# sub-1Ghz_radio.net
KiCad netlist of a schematic drawn in Altium Designer
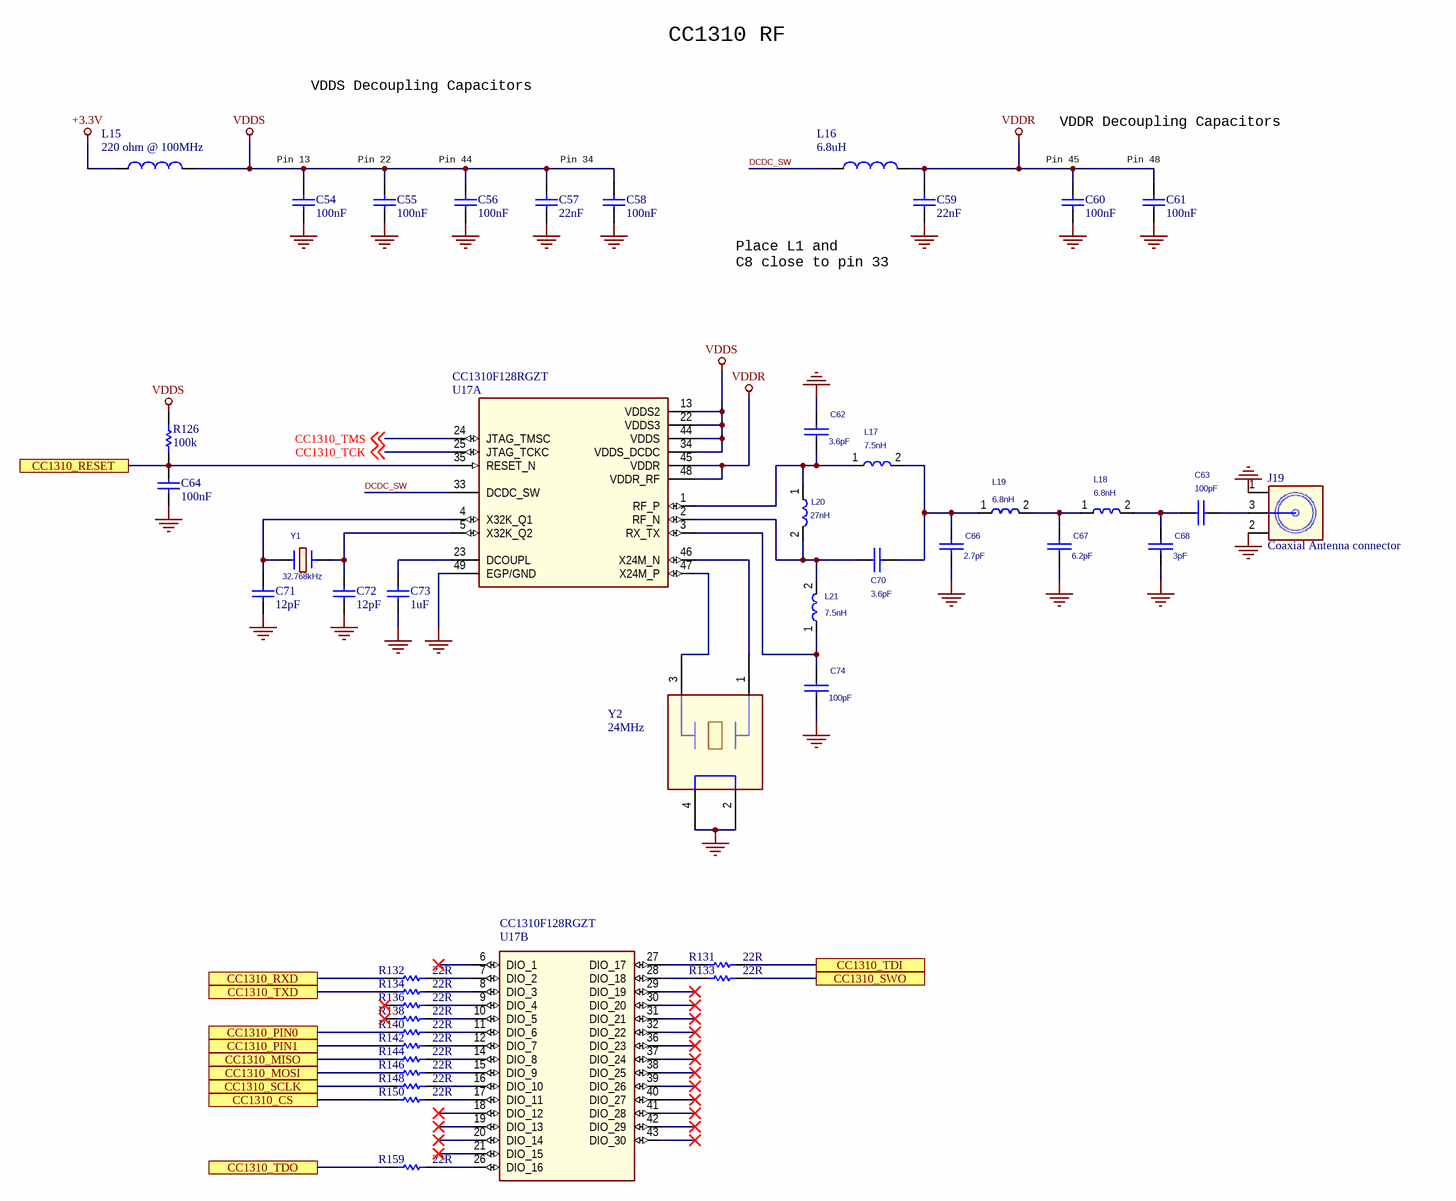
[diagram p0: sub-1Ghz_radio.SchDoc]

(export (version "E")
  (design (tool "Eeschema 10.0.6"))
  (components
    (comp (ref "C54")
      (value "100nF")
      (footprint "0603_[1608]")
      (description "Ceramic X7R 50V")
      (fields (field (name "PUBLISHER") "Altium Limited"))
      (libsource (lib "DEVELER_Library") (part "Cap"))
    )
    (comp (ref "C55")
      (value "100nF")
      (footprint "0603_[1608]")
      (description "Ceramic X7R 50V")
      (fields (field (name "PUBLISHER") "Altium Limited"))
      (libsource (lib "DEVELER_Library") (part "Cap"))
    )
    (comp (ref "C56")
      (value "100nF")
      (footprint "0603_[1608]")
      (description "Ceramic X7R 50V")
      (fields (field (name "PUBLISHER") "Altium Limited"))
      (libsource (lib "DEVELER_Library") (part "Cap"))
    )
    (comp (ref "C57")
      (value "22nF")
      (footprint "0603_[1608]")
      (description "Ceramic X7R 50V")
      (fields (field (name "PUBLISHER") "Altium Limited"))
      (libsource (lib "DEVELER_Library") (part "Cap"))
    )
    (comp (ref "C58")
      (value "100nF")
      (footprint "0603_[1608]")
      (description "Ceramic X7R 50V")
      (fields (field (name "PUBLISHER") "Altium Limited"))
      (libsource (lib "DEVELER_Library") (part "Cap"))
    )
    (comp (ref "C59")
      (value "22nF")
      (footprint "0603_[1608]")
      (description "Ceramic X7R 50V")
      (fields (field (name "PUBLISHER") "Altium Limited"))
      (libsource (lib "DEVELER_Library") (part "Cap"))
    )
    (comp (ref "C60")
      (value "100nF")
      (footprint "0603_[1608]")
      (description "Ceramic X7R 50V")
      (fields (field (name "PUBLISHER") "Altium Limited"))
      (libsource (lib "DEVELER_Library") (part "Cap"))
    )
    (comp (ref "C61")
      (value "100nF")
      (footprint "0603_[1608]")
      (description "Ceramic X7R 50V")
      (fields (field (name "PUBLISHER") "Altium Limited"))
      (libsource (lib "DEVELER_Library") (part "Cap"))
    )
    (comp (ref "C62")
      (value "3.6pF")
      (footprint "0402_[1005]")
      (description "CAPACITOR, CERAMIC C0G/NP0, 3.6pF, 50V, -0.25pF/+0.25pF, -55DEGC/+125DEGC, 0402, SMD")
      (fields (field (name "VOLTAGE") "CMAX") (field (name "VENDOR PART NUMBER") "GRM1555C1H3R6CA01D"))
      (libsource (lib "*") (part "CAPACITOR"))
    )
    (comp (ref "C63")
      (value "100pF")
      (footprint "0402_[1005]")
      (description "Ceramic COG 50V")
      (fields (field (name "VOLTAGE") "CMAX") (field (name "VENDOR PART NUMBER") "GRM1555C1H101JA01D"))
      (libsource (lib "*") (part "CAPACITOR"))
    )
    (comp (ref "C64")
      (value "100nF")
      (footprint "0603_[1608]")
      (description "Ceramic X7R 50V")
      (fields (field (name "PUBLISHER") "Altium Limited"))
      (libsource (lib "DEVELER_Library") (part "Cap"))
    )
    (comp (ref "C66")
      (value "2.7pF")
      (footprint "0402_[1005]")
      (description "CAPACITOR, CERAMIC C0G/NP0, 2.7pF, 50V, -0.25pF/+0.25pF, -55DEGC/+125DEGC, 0402, SMD")
      (fields (field (name "VOLTAGE") "CMAX") (field (name "MPN") "GRM1555C1H2R7CA01D"))
      (libsource (lib "*") (part "CAPACITOR"))
    )
    (comp (ref "C67")
      (value "6.2pF")
      (footprint "0402_[1005]")
      (description "CAPACITOR, CERAMIC C0G/NP0, 6.2pF, 50V, -0.25pF/+0.25pF, -55DEGC/+125DEGC, 0402, SMD")
      (fields (field (name "VOLTAGE") "CMAX") (field (name "MPN") "GRM1555C1H6R2CA01D"))
      (libsource (lib "*") (part "CAPACITOR"))
    )
    (comp (ref "C68")
      (value "3pF")
      (footprint "0402_[1005]")
      (description "CAPACITOR, CERAMIC C0G/NP0, 3pF, 50V, -0.25pF/+0.25pF, -55DEGC/+125DEGC, 0402, SMD")
      (fields (field (name "VOLTAGE") "CMAX") (field (name "MPN") "GRM1555C1H3R0CA01D"))
      (libsource (lib "*") (part "CAPACITOR"))
    )
    (comp (ref "C70")
      (value "3.6pF")
      (footprint "0402_[1005]")
      (description "CAPACITOR, CERAMIC C0G/NP0, 3.6pF, 50V, -0.25pF/+0.25pF, -55DEGC/+125DEGC, 0402, SMD")
      (fields (field (name "VOLTAGE") "CMAX") (field (name "VENDOR PART NUMBER") "GRM1555C1H3R6CA01D"))
      (libsource (lib "*") (part "CAPACITOR"))
    )
    (comp (ref "C71")
      (value "12pF")
      (footprint "0603_[1608]")
      (description "Ceramic X7R 50V")
      (fields (field (name "PUBLISHER") "Altium Limited"))
      (libsource (lib "DEVELER_Library") (part "Cap"))
    )
    (comp (ref "C72")
      (value "12pF")
      (footprint "0603_[1608]")
      (description "Ceramic X7R 50V")
      (fields (field (name "PUBLISHER") "Altium Limited"))
      (libsource (lib "DEVELER_Library") (part "Cap"))
    )
    (comp (ref "C73")
      (value "1uF")
      (footprint "0805_[2012]")
      (description "Ceramic X7R 50V")
      (fields (field (name "PUBLISHER") "Altium Limited"))
      (libsource (lib "DEVELER_Library") (part "Cap"))
    )
    (comp (ref "C74")
      (value "100pF")
      (footprint "0402_[1005]")
      (description "Ceramic COG 50V")
      (fields (field (name "VOLTAGE") "CMAX") (field (name "VENDOR PART NUMBER") "GRM1555C1H101JA01D"))
      (libsource (lib "*") (part "CAPACITOR"))
    )
    (comp (ref "J19")
      (value "Coaxial Antenna connector")
      (footprint "U.FL_COAXIAL_2.6x2.6MM_STRAIGHT_SMD")
      (description "U.FL serias")
      (libsource (lib "develer_library") (part "ANTENNA_3P_COAXIAL_CONNECTOR"))
    )
    (comp (ref "L15")
      (value "220 ohm @ 100MHz")
      (footprint "0805_[2012]")
      (description "WE 742792022")
      (libsource (lib "DEVELER_Library") (part "Ferrite Bead"))
    )
    (comp (ref "L16")
      (value "6.8uH")
      (footprint "0805_[2012]")
      (description "Inductor WE 742792022")
      (libsource (lib "DEVELER_Library") (part "Inductor"))
    )
    (comp (ref "L17")
      (value "7.5nH")
      (footprint "0402_[1005]")
      (description "INDUCTOR, RF, CHIP, NON-MAGNETIC CORE, 7.5nH, -5%/+5%, 0.3A, -55DEGC/+125DEGC, 0402, SMD")
      (fields (field (name "PART NUMBER") "03-07533") (field (name "VENDOR PART NUMBER") "LQG15HS7N5J02D"))
      (libsource (lib "*") (part "INDUCTOR"))
    )
    (comp (ref "L18")
      (value "6.8nH")
      (footprint "0402_[1005]")
      (description "INDUCTOR, RF, CHIP, NON-MAGNETIC CORE, 6.8nH, -5%/+5%, 0.3A, -55DEGC/+125DEGC, 0402, SMD")
      (fields (field (name "VENDOR PART NUMBER") "LQG15HS6N8J02D") (field (name "PART NUMBER") "03-07532"))
      (libsource (lib "*") (part "INDUCTOR"))
    )
    (comp (ref "L19")
      (value "6.8nH")
      (footprint "0402_[1005]")
      (description "INDUCTOR, RF, CHIP, NON-MAGNETIC CORE, 6.8nH, -5%/+5%, 0.3A, -55DEGC/+125DEGC, 0402, SMD")
      (fields (field (name "VENDOR PART NUMBER") "LQG15HS6N8J02D") (field (name "PART NUMBER") "03-07532"))
      (libsource (lib "*") (part "INDUCTOR"))
    )
    (comp (ref "L20")
      (value "27nH")
      (footprint "0402_[1005]")
      (description "INDUCTOR, RF, CHIP, NON-MAGNETIC CORE, 27nH, -5%/+5%, 0.3A, -55DEGC/+125DEGC, 0402, SMD")
      (fields (field (name "VENDOR PART NUMBER") "LQG15HS27NJ02D") (field (name "PART NUMBER") "03-07528"))
      (libsource (lib "*") (part "INDUCTOR"))
    )
    (comp (ref "L21")
      (value "7.5nH")
      (footprint "0402_[1005]")
      (description "INDUCTOR, RF, CHIP, NON-MAGNETIC CORE, 7.5nH, -5%/+5%, 0.3A, -55DEGC/+125DEGC, 0402, SMD")
      (fields (field (name "PART NUMBER") "03-07533") (field (name "VENDOR PART NUMBER") "LQG15HS7N5J02D"))
      (libsource (lib "*") (part "INDUCTOR"))
    )
    (comp (ref "R126")
      (value "100k")
      (footprint "0603_[1608]")
      (description "Resistor")
      (fields (field (name "PUBLISHER") "Altium Limited"))
      (libsource (lib "project42_lib") (part "Res1"))
    )
    (comp (ref "R131")
      (value "22R")
      (footprint "0603_[1608]")
      (description "Resistor")
      (fields (field (name "PUBLISHER") "Altium Limited"))
      (libsource (lib "DEVELER_Library") (part "Res1"))
    )
    (comp (ref "R132")
      (value "22R")
      (footprint "0603_[1608]")
      (description "Resistor")
      (fields (field (name "PUBLISHER") "Altium Limited"))
      (libsource (lib "DEVELER_Library") (part "Res1"))
    )
    (comp (ref "R133")
      (value "22R")
      (footprint "0603_[1608]")
      (description "Resistor")
      (fields (field (name "PUBLISHER") "Altium Limited"))
      (libsource (lib "DEVELER_Library") (part "Res1"))
    )
    (comp (ref "R134")
      (value "22R")
      (footprint "0603_[1608]")
      (description "Resistor")
      (fields (field (name "PUBLISHER") "Altium Limited"))
      (libsource (lib "DEVELER_Library") (part "Res1"))
    )
    (comp (ref "R136")
      (value "22R")
      (footprint "0603_[1608]")
      (description "Resistor")
      (fields (field (name "PUBLISHER") "Altium Limited"))
      (libsource (lib "DEVELER_Library") (part "Res1"))
    )
    (comp (ref "R138")
      (value "22R")
      (footprint "0603_[1608]")
      (description "Resistor")
      (fields (field (name "PUBLISHER") "Altium Limited"))
      (libsource (lib "DEVELER_Library") (part "Res1"))
    )
    (comp (ref "R140")
      (value "22R")
      (footprint "0603_[1608]")
      (description "Resistor")
      (fields (field (name "PUBLISHER") "Altium Limited"))
      (libsource (lib "DEVELER_Library") (part "Res1"))
    )
    (comp (ref "R142")
      (value "22R")
      (footprint "0603_[1608]")
      (description "Resistor")
      (fields (field (name "PUBLISHER") "Altium Limited"))
      (libsource (lib "DEVELER_Library") (part "Res1"))
    )
    (comp (ref "R144")
      (value "22R")
      (footprint "0603_[1608]")
      (description "Resistor")
      (fields (field (name "PUBLISHER") "Altium Limited"))
      (libsource (lib "DEVELER_Library") (part "Res1"))
    )
    (comp (ref "R146")
      (value "22R")
      (footprint "0603_[1608]")
      (description "Resistor")
      (fields (field (name "PUBLISHER") "Altium Limited"))
      (libsource (lib "DEVELER_Library") (part "Res1"))
    )
    (comp (ref "R148")
      (value "22R")
      (footprint "0603_[1608]")
      (description "Resistor")
      (fields (field (name "PUBLISHER") "Altium Limited"))
      (libsource (lib "DEVELER_Library") (part "Res1"))
    )
    (comp (ref "R150")
      (value "22R")
      (footprint "0603_[1608]")
      (description "Resistor")
      (fields (field (name "PUBLISHER") "Altium Limited"))
      (libsource (lib "DEVELER_Library") (part "Res1"))
    )
    (comp (ref "R159")
      (value "22R")
      (footprint "0603_[1608]")
      (description "Resistor")
      (fields (field (name "PUBLISHER") "Altium Limited"))
      (libsource (lib "DEVELER_Library") (part "Res1"))
    )
    (comp (ref "U17")
      (value "CC1310F128RGZT")
      (footprint "PQFN50P700X700X100-48N")
      (description "Texas CC1310 RF Cpu")
      (fields (field (name "DESIGNED_BY") "Artur Bielinski"))
      (libsource (lib "develer_library") (part "CC1310F128RGZT_VQFN48"))
    )
    (comp (ref "Y1")
      (value "32.768kHz")
      (footprint "CRYSTAL_3.2X1.5MM_2P_SMD")
      (description "CRYSTAL, RESONATOR, 32.768kHz, -20PPM/+20PPM, -40DEGC/+85DEGC, SMD")
      (fields (field (name "MPN") "FC-135 32.7680KA-AG0") (field (name "MANUFACTURER") "EPSON"))
      (libsource (lib "*") (part "CRYSTAL"))
    )
    (comp (ref "Y2")
      (value "24MHz")
      (footprint "CRYSTAL_3.2X2.5MM_4P_SMD")
      (description "Crystal")
      (libsource (lib "develer_library") (part "CRYSTAL-4p"))
    )
  )
  (nets
    (net (code "1") (name "+3.3V") (class "Default")
      (node (ref "L15") (pin "2") (pinfunction "2_2") (pintype "passive"))
    )
    (net (code "2") (name "/CC1310_CS") (class "Default")
      (node (ref "R150") (pin "2") (pinfunction "2_2") (pintype "passive"))
    )
    (net (code "3") (name "/CC1310_MISO") (class "Default")
      (node (ref "R144") (pin "2") (pinfunction "2_2") (pintype "passive"))
    )
    (net (code "4") (name "/CC1310_MOSI") (class "Default")
      (node (ref "R146") (pin "2") (pinfunction "2_2") (pintype "passive"))
    )
    (net (code "5") (name "/CC1310_PIN0") (class "Default")
      (node (ref "R140") (pin "2") (pinfunction "2_2") (pintype "passive"))
    )
    (net (code "6") (name "/CC1310_PIN1") (class "Default")
      (node (ref "R142") (pin "2") (pinfunction "2_2") (pintype "passive"))
    )
    (net (code "7") (name "/CC1310_RESET") (class "Default")
      (node (ref "C64") (pin "2") (pinfunction "2_2") (pintype "passive"))
      (node (ref "R126") (pin "2") (pinfunction "2_2") (pintype "passive"))
      (node (ref "U17") (pin "35") (pinfunction "RESET_N_35") (pintype "input"))
    )
    (net (code "8") (name "/CC1310_RXD") (class "Default")
      (node (ref "R132") (pin "2") (pinfunction "2_2") (pintype "passive"))
    )
    (net (code "9") (name "/CC1310_SCLK") (class "Default")
      (node (ref "R148") (pin "2") (pinfunction "2_2") (pintype "passive"))
    )
    (net (code "10") (name "/CC1310_SWO") (class "Default")
      (node (ref "R133") (pin "1") (pinfunction "1_1") (pintype "passive"))
    )
    (net (code "11") (name "/CC1310_TDI") (class "Default")
      (node (ref "R131") (pin "1") (pinfunction "1_1") (pintype "passive"))
    )
    (net (code "12") (name "/CC1310_TDO") (class "Default")
      (node (ref "R159") (pin "2") (pinfunction "2_2") (pintype "passive"))
    )
    (net (code "13") (name "/CC1310_TXD") (class "Default")
      (node (ref "R134") (pin "2") (pinfunction "2_2") (pintype "passive"))
    )
    (net (code "14") (name "/DCDC_SW") (class "Default")
      (node (ref "L16") (pin "2") (pinfunction "2_2") (pintype "passive"))
      (node (ref "U17") (pin "33") (pinfunction "DCDC_SW_33") (pintype "power_in"))
    )
    (net (code "15") (name "CC1310_TCK") (class "Default")
      (node (ref "U17") (pin "25") (pinfunction "JTAG_TCKC_25") (pintype "bidirectional"))
    )
    (net (code "16") (name "CC1310_TMS") (class "Default")
      (node (ref "U17") (pin "24") (pinfunction "JTAG_TMSC_24") (pintype "bidirectional"))
    )
    (net (code "17") (name "GND") (class "Default")
      (node (ref "C54") (pin "1") (pinfunction "1_1") (pintype "passive"))
      (node (ref "C55") (pin "1") (pinfunction "1_1") (pintype "passive"))
      (node (ref "C56") (pin "1") (pinfunction "1_1") (pintype "passive"))
      (node (ref "C57") (pin "1") (pinfunction "1_1") (pintype "passive"))
      (node (ref "C58") (pin "1") (pinfunction "1_1") (pintype "passive"))
      (node (ref "C59") (pin "1") (pinfunction "1_1") (pintype "passive"))
      (node (ref "C60") (pin "1") (pinfunction "1_1") (pintype "passive"))
      (node (ref "C61") (pin "1") (pinfunction "1_1") (pintype "passive"))
      (node (ref "C62") (pin "1") (pinfunction "1_1") (pintype "passive"))
      (node (ref "C64") (pin "1") (pinfunction "1_1") (pintype "passive"))
      (node (ref "C66") (pin "2") (pinfunction "2_2") (pintype "passive"))
      (node (ref "C67") (pin "2") (pinfunction "2_2") (pintype "passive"))
      (node (ref "C68") (pin "2") (pinfunction "2_2") (pintype "passive"))
      (node (ref "C71") (pin "1") (pinfunction "1_1") (pintype "passive"))
      (node (ref "C72") (pin "1") (pinfunction "1_1") (pintype "passive"))
      (node (ref "C73") (pin "1") (pinfunction "1_1") (pintype "passive"))
      (node (ref "C74") (pin "2") (pinfunction "2_2") (pintype "passive"))
      (node (ref "J19") (pin "1") (pinfunction "GND_1") (pintype "passive"))
      (node (ref "J19") (pin "2") (pinfunction "GND_2") (pintype "passive"))
      (node (ref "U17") (pin "49") (pinfunction "EGP/GND_49") (pintype "power_in"))
      (node (ref "Y2") (pin "2") (pinfunction "2_2") (pintype "passive"))
      (node (ref "Y2") (pin "4") (pinfunction "4_4") (pintype "passive"))
    )
    (net (code "18") (name "Net-(C63-Pad1)") (class "Default")
      (node (ref "C63") (pin "1") (pinfunction "1_1") (pintype "passive"))
      (node (ref "C68") (pin "1") (pinfunction "1_1") (pintype "passive"))
      (node (ref "L18") (pin "2") (pinfunction "2_2") (pintype "passive"))
    )
    (net (code "19") (name "Net-(C66-Pad1)") (class "Default")
      (node (ref "C66") (pin "1") (pinfunction "1_1") (pintype "passive"))
      (node (ref "C70") (pin "2") (pinfunction "2_2") (pintype "passive"))
      (node (ref "L17") (pin "2") (pinfunction "2_2") (pintype "passive"))
      (node (ref "L19") (pin "1") (pinfunction "1_1") (pintype "passive"))
    )
    (net (code "20") (name "Net-(C67-Pad1)") (class "Default")
      (node (ref "C67") (pin "1") (pinfunction "1_1") (pintype "passive"))
      (node (ref "L18") (pin "1") (pinfunction "1_1") (pintype "passive"))
      (node (ref "L19") (pin "2") (pinfunction "2_2") (pintype "passive"))
    )
    (net (code "21") (name "Net-(J19-SIG)") (class "Default")
      (node (ref "C63") (pin "2") (pinfunction "2_2") (pintype "passive"))
      (node (ref "J19") (pin "3") (pinfunction "SIG_3") (pintype "passive"))
    )
    (net (code "22") (name "Net-(U17A-DCOUPL)") (class "Default")
      (node (ref "C73") (pin "2") (pinfunction "2_2") (pintype "passive"))
      (node (ref "U17") (pin "23") (pinfunction "DCOUPL_23") (pintype "power_in"))
    )
    (net (code "23") (name "Net-(U17A-RF_N)") (class "Default")
      (node (ref "C70") (pin "1") (pinfunction "1_1") (pintype "passive"))
      (node (ref "L20") (pin "2") (pinfunction "2_2") (pintype "passive"))
      (node (ref "L21") (pin "2") (pinfunction "2_2") (pintype "passive"))
      (node (ref "U17") (pin "2") (pinfunction "RF_N_2") (pintype "bidirectional"))
    )
    (net (code "24") (name "Net-(U17A-RF_P)") (class "Default")
      (node (ref "C62") (pin "2") (pinfunction "2_2") (pintype "passive"))
      (node (ref "L17") (pin "1") (pinfunction "1_1") (pintype "passive"))
      (node (ref "L20") (pin "1") (pinfunction "1_1") (pintype "passive"))
      (node (ref "U17") (pin "1") (pinfunction "RF_P_1") (pintype "bidirectional"))
    )
    (net (code "25") (name "Net-(U17A-RX_TX)") (class "Default")
      (node (ref "C74") (pin "1") (pinfunction "1_1") (pintype "passive"))
      (node (ref "L21") (pin "1") (pinfunction "1_1") (pintype "passive"))
      (node (ref "U17") (pin "3") (pinfunction "RX_TX_3") (pintype "bidirectional"))
    )
    (net (code "26") (name "Net-(U17A-X24M_N)") (class "Default")
      (node (ref "U17") (pin "46") (pinfunction "X24M_N_46") (pintype "bidirectional"))
      (node (ref "Y2") (pin "1") (pinfunction "1_1") (pintype "passive"))
    )
    (net (code "27") (name "Net-(U17A-X24M_P)") (class "Default")
      (node (ref "U17") (pin "47") (pinfunction "X24M_P_47") (pintype "bidirectional"))
      (node (ref "Y2") (pin "3") (pinfunction "3_3") (pintype "passive"))
    )
    (net (code "28") (name "Net-(U17A-X32K_Q1)") (class "Default")
      (node (ref "C71") (pin "2") (pinfunction "2_2") (pintype "passive"))
      (node (ref "U17") (pin "4") (pinfunction "X32K_Q1_4") (pintype "bidirectional"))
      (node (ref "Y1") (pin "1") (pinfunction "1_1") (pintype "passive"))
    )
    (net (code "29") (name "Net-(U17A-X32K_Q2)") (class "Default")
      (node (ref "C72") (pin "2") (pinfunction "2_2") (pintype "passive"))
      (node (ref "U17") (pin "5") (pinfunction "X32K_Q2_5") (pintype "bidirectional"))
      (node (ref "Y1") (pin "2") (pinfunction "2_2") (pintype "passive"))
    )
    (net (code "30") (name "Net-(U17B-DIO_2)") (class "Default")
      (node (ref "R132") (pin "1") (pinfunction "1_1") (pintype "passive"))
      (node (ref "U17") (pin "7") (pinfunction "DIO_2_7") (pintype "bidirectional"))
    )
    (net (code "31") (name "Net-(U17B-DIO_3)") (class "Default")
      (node (ref "R134") (pin "1") (pinfunction "1_1") (pintype "passive"))
      (node (ref "U17") (pin "8") (pinfunction "DIO_3_8") (pintype "bidirectional"))
    )
    (net (code "32") (name "Net-(U17B-DIO_4)") (class "Default")
      (node (ref "R136") (pin "1") (pinfunction "1_1") (pintype "passive"))
      (node (ref "U17") (pin "9") (pinfunction "DIO_4_9") (pintype "bidirectional"))
    )
    (net (code "33") (name "Net-(U17B-DIO_5)") (class "Default")
      (node (ref "R138") (pin "1") (pinfunction "1_1") (pintype "passive"))
      (node (ref "U17") (pin "10") (pinfunction "DIO_5_10") (pintype "bidirectional"))
    )
    (net (code "34") (name "Net-(U17B-DIO_6)") (class "Default")
      (node (ref "R140") (pin "1") (pinfunction "1_1") (pintype "passive"))
      (node (ref "U17") (pin "11") (pinfunction "DIO_6_11") (pintype "bidirectional"))
    )
    (net (code "35") (name "Net-(U17B-DIO_7)") (class "Default")
      (node (ref "R142") (pin "1") (pinfunction "1_1") (pintype "passive"))
      (node (ref "U17") (pin "12") (pinfunction "DIO_7_12") (pintype "bidirectional"))
    )
    (net (code "36") (name "Net-(U17B-DIO_8)") (class "Default")
      (node (ref "R144") (pin "1") (pinfunction "1_1") (pintype "passive"))
      (node (ref "U17") (pin "14") (pinfunction "DIO_8_14") (pintype "bidirectional"))
    )
    (net (code "37") (name "Net-(U17B-DIO_9)") (class "Default")
      (node (ref "R146") (pin "1") (pinfunction "1_1") (pintype "passive"))
      (node (ref "U17") (pin "15") (pinfunction "DIO_9_15") (pintype "bidirectional"))
    )
    (net (code "38") (name "Net-(U17B-DIO_10)") (class "Default")
      (node (ref "R148") (pin "1") (pinfunction "1_1") (pintype "passive"))
      (node (ref "U17") (pin "16") (pinfunction "DIO_10_16") (pintype "bidirectional"))
    )
    (net (code "39") (name "Net-(U17B-DIO_11)") (class "Default")
      (node (ref "R150") (pin "1") (pinfunction "1_1") (pintype "passive"))
      (node (ref "U17") (pin "17") (pinfunction "DIO_11_17") (pintype "bidirectional"))
    )
    (net (code "40") (name "Net-(U17B-DIO_16)") (class "Default")
      (node (ref "R159") (pin "1") (pinfunction "1_1") (pintype "passive"))
      (node (ref "U17") (pin "26") (pinfunction "DIO_16_26") (pintype "bidirectional"))
    )
    (net (code "41") (name "Net-(U17B-DIO_17)") (class "Default")
      (node (ref "R131") (pin "2") (pinfunction "2_2") (pintype "passive"))
      (node (ref "U17") (pin "27") (pinfunction "DIO_17_27") (pintype "bidirectional"))
    )
    (net (code "42") (name "Net-(U17B-DIO_18)") (class "Default")
      (node (ref "R133") (pin "2") (pinfunction "2_2") (pintype "passive"))
      (node (ref "U17") (pin "28") (pinfunction "DIO_18_28") (pintype "bidirectional"))
    )
    (net (code "43") (name "VDDR") (class "Default")
      (node (ref "C59") (pin "2") (pinfunction "2_2") (pintype "passive"))
      (node (ref "C60") (pin "2") (pinfunction "2_2") (pintype "passive"))
      (node (ref "C61") (pin "2") (pinfunction "2_2") (pintype "passive"))
      (node (ref "L16") (pin "1") (pinfunction "1_1") (pintype "passive"))
      (node (ref "U17") (pin "45") (pinfunction "VDDR_45") (pintype "power_in"))
      (node (ref "U17") (pin "48") (pinfunction "VDDR_RF_48") (pintype "power_in"))
    )
    (net (code "44") (name "VDDS") (class "Default")
      (node (ref "C54") (pin "2") (pinfunction "2_2") (pintype "passive"))
      (node (ref "C55") (pin "2") (pinfunction "2_2") (pintype "passive"))
      (node (ref "C56") (pin "2") (pinfunction "2_2") (pintype "passive"))
      (node (ref "C57") (pin "2") (pinfunction "2_2") (pintype "passive"))
      (node (ref "C58") (pin "2") (pinfunction "2_2") (pintype "passive"))
      (node (ref "L15") (pin "1") (pinfunction "1_1") (pintype "passive"))
      (node (ref "R126") (pin "1") (pinfunction "1_1") (pintype "passive"))
      (node (ref "U17") (pin "13") (pinfunction "VDDS2_13") (pintype "power_in"))
      (node (ref "U17") (pin "22") (pinfunction "VDDS3_22") (pintype "power_in"))
      (node (ref "U17") (pin "34") (pinfunction "VDDS_DCDC_34") (pintype "power_in"))
      (node (ref "U17") (pin "44") (pinfunction "VDDS_44") (pintype "power_in"))
    )
    (net (code "45") (name "unconnected-(R136-Pad2)") (class "Default")
      (node (ref "R136") (pin "2") (pinfunction "2_2") (pintype "passive+no_connect"))
    )
    (net (code "46") (name "unconnected-(R138-Pad2)") (class "Default")
      (node (ref "R138") (pin "2") (pinfunction "2_2") (pintype "passive+no_connect"))
    )
    (net (code "47") (name "unconnected-(U17B-DIO_1-Pad6)") (class "Default")
      (node (ref "U17") (pin "6") (pinfunction "DIO_1_6") (pintype "bidirectional+no_connect"))
    )
    (net (code "48") (name "unconnected-(U17B-DIO_12-Pad18)") (class "Default")
      (node (ref "U17") (pin "18") (pinfunction "DIO_12_18") (pintype "bidirectional+no_connect"))
    )
    (net (code "49") (name "unconnected-(U17B-DIO_13-Pad19)") (class "Default")
      (node (ref "U17") (pin "19") (pinfunction "DIO_13_19") (pintype "bidirectional+no_connect"))
    )
    (net (code "50") (name "unconnected-(U17B-DIO_14-Pad20)") (class "Default")
      (node (ref "U17") (pin "20") (pinfunction "DIO_14_20") (pintype "bidirectional+no_connect"))
    )
    (net (code "51") (name "unconnected-(U17B-DIO_15-Pad21)") (class "Default")
      (node (ref "U17") (pin "21") (pinfunction "DIO_15_21") (pintype "bidirectional+no_connect"))
    )
    (net (code "52") (name "unconnected-(U17B-DIO_19-Pad29)") (class "Default")
      (node (ref "U17") (pin "29") (pinfunction "DIO_19_29") (pintype "bidirectional+no_connect"))
    )
    (net (code "53") (name "unconnected-(U17B-DIO_20-Pad30)") (class "Default")
      (node (ref "U17") (pin "30") (pinfunction "DIO_20_30") (pintype "bidirectional+no_connect"))
    )
    (net (code "54") (name "unconnected-(U17B-DIO_21-Pad31)") (class "Default")
      (node (ref "U17") (pin "31") (pinfunction "DIO_21_31") (pintype "bidirectional+no_connect"))
    )
    (net (code "55") (name "unconnected-(U17B-DIO_22-Pad32)") (class "Default")
      (node (ref "U17") (pin "32") (pinfunction "DIO_22_32") (pintype "bidirectional+no_connect"))
    )
    (net (code "56") (name "unconnected-(U17B-DIO_23-Pad36)") (class "Default")
      (node (ref "U17") (pin "36") (pinfunction "DIO_23_36") (pintype "bidirectional+no_connect"))
    )
    (net (code "57") (name "unconnected-(U17B-DIO_24-Pad37)") (class "Default")
      (node (ref "U17") (pin "37") (pinfunction "DIO_24_37") (pintype "bidirectional+no_connect"))
    )
    (net (code "58") (name "unconnected-(U17B-DIO_25-Pad38)") (class "Default")
      (node (ref "U17") (pin "38") (pinfunction "DIO_25_38") (pintype "bidirectional+no_connect"))
    )
    (net (code "59") (name "unconnected-(U17B-DIO_26-Pad39)") (class "Default")
      (node (ref "U17") (pin "39") (pinfunction "DIO_26_39") (pintype "bidirectional+no_connect"))
    )
    (net (code "60") (name "unconnected-(U17B-DIO_27-Pad40)") (class "Default")
      (node (ref "U17") (pin "40") (pinfunction "DIO_27_40") (pintype "bidirectional+no_connect"))
    )
    (net (code "61") (name "unconnected-(U17B-DIO_28-Pad41)") (class "Default")
      (node (ref "U17") (pin "41") (pinfunction "DIO_28_41") (pintype "bidirectional+no_connect"))
    )
    (net (code "62") (name "unconnected-(U17B-DIO_29-Pad42)") (class "Default")
      (node (ref "U17") (pin "42") (pinfunction "DIO_29_42") (pintype "bidirectional+no_connect"))
    )
    (net (code "63") (name "unconnected-(U17B-DIO_30-Pad43)") (class "Default")
      (node (ref "U17") (pin "43") (pinfunction "DIO_30_43") (pintype "bidirectional+no_connect"))
    )
  )
)
